# WallBaseBoard.net
KiCad netlist of a schematic drawn in Altium Designer
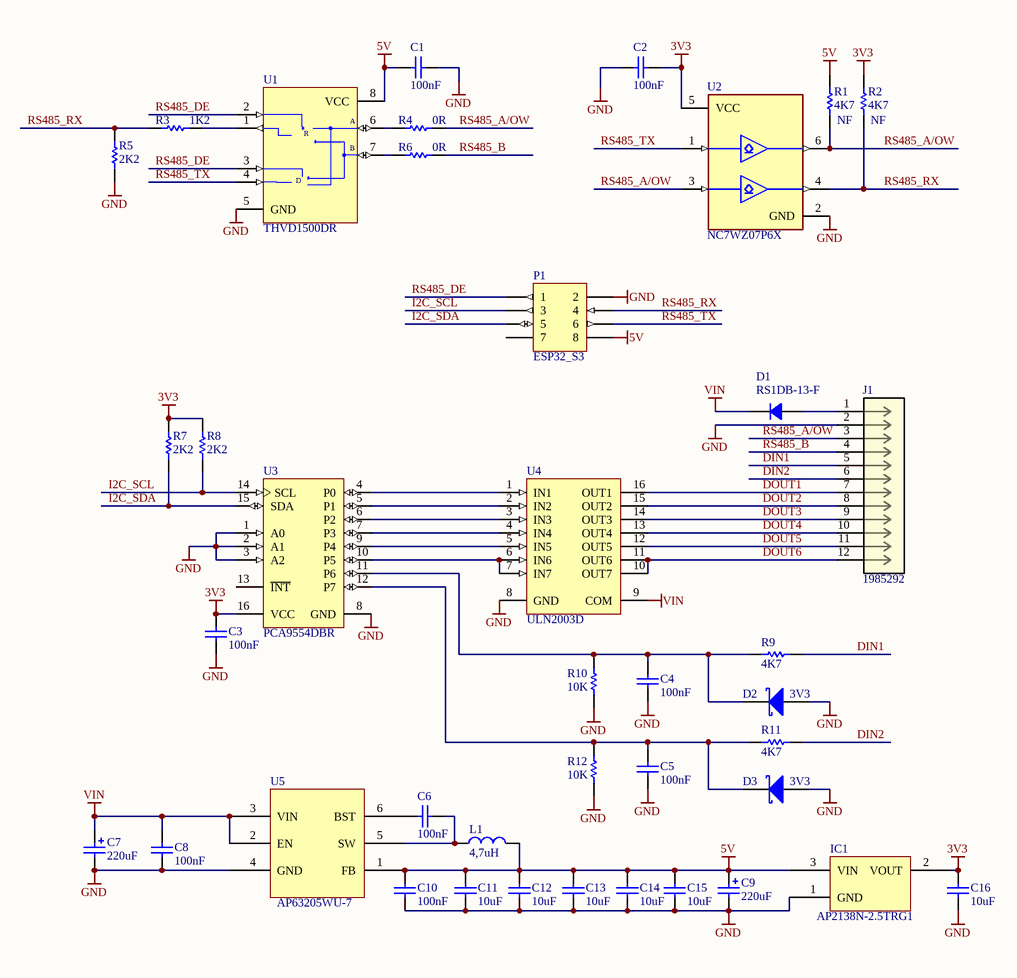
[diagram p0: WallBaseBoard.SchDoc]

(export (version "E")
  (design (tool "Eeschema 10.0.6"))
  (components
    (comp (ref "C1")
      (value "100nF")
      (footprint "0603")
      (description "Ceramic Chip Capacitor - Standard")
      (fields (field (name "PUBLISHER") "Altium Limited"))
      (libsource (lib "DE-211024") (part "C0603"))
    )
    (comp (ref "C2")
      (value "100nF")
      (footprint "0603")
      (description "Ceramic Chip Capacitor - Standard")
      (fields (field (name "PUBLISHER") "Altium Limited"))
      (libsource (lib "DE-211024") (part "C0603"))
    )
    (comp (ref "C3")
      (value "100nF")
      (footprint "0603")
      (description "Ceramic Chip Capacitor - Standard")
      (fields (field (name "PUBLISHER") "Altium Limited"))
      (libsource (lib "DE-211024") (part "C0603"))
    )
    (comp (ref "C4")
      (value "100nF")
      (footprint "0603")
      (description "Ceramic Chip Capacitor - Standard")
      (fields (field (name "PUBLISHER") "Altium Limited"))
      (libsource (lib "DE-211024") (part "C0603"))
    )
    (comp (ref "C5")
      (value "100nF")
      (footprint "0603")
      (description "Ceramic Chip Capacitor - Standard")
      (fields (field (name "PUBLISHER") "Altium Limited"))
      (libsource (lib "DE-211024") (part "C0603"))
    )
    (comp (ref "C6")
      (value "100nF")
      (footprint "0603")
      (description "Ceramic Chip Capacitor - Standard")
      (fields (field (name "PUBLISHER") "Altium Limited"))
      (libsource (lib "DE-211024") (part "C0603"))
    )
    (comp (ref "C7")
      (value "220uF")
      (footprint "SMD,D8xL10.2mm")
      (description "220uF 35V 195mA@120Hz ±20% SMD,D8xL10.2mm Aluminum Electrolytic Capacitors - SMD ROHS")
      (fields (field (name "PUBLISHER") "Altium Limited"))
      (libsource (lib "DE-211024") (part "ROQANG VT1V221M0810"))
    )
    (comp (ref "C8")
      (value "100nF")
      (footprint "0603")
      (description "Ceramic Chip Capacitor - Standard")
      (fields (field (name "PUBLISHER") "Altium Limited"))
      (libsource (lib "DE-211024") (part "C0603"))
    )
    (comp (ref "C9")
      (value "220uF")
      (footprint "SMD,D6.3xL7.7mm Aluminum Electrolytic Capacitors")
      (description "220uF 16V 110mA@120Hz ±20% SMD,D6.3xL7.7mm Aluminum Electrolytic Capacitors - SMD ROHS")
      (fields (field (name "Comment") "ROQANG VT1C221M0607_1") (field (name "PUBLISHER") "Altium Limited"))
      (libsource (lib "DE-211024") (part "ROQANG VT1C221M0607_1"))
    )
    (comp (ref "C10")
      (value "100nF")
      (footprint "0603")
      (description "Ceramic Chip Capacitor - Standard")
      (fields (field (name "PUBLISHER") "Altium Limited"))
      (libsource (lib "DE-211024") (part "C0603"))
    )
    (comp (ref "C11")
      (value "10uF")
      (footprint "0805")
      (description "Ceramic Chip Capacitor - Standard")
      (fields (field (name "Comment") "4u7") (field (name "PUBLISHER") "Altium Limited"))
      (libsource (lib "DE-211024") (part "C0805"))
    )
    (comp (ref "C12")
      (value "10uF")
      (footprint "0805")
      (description "Ceramic Chip Capacitor - Standard")
      (fields (field (name "Comment") "4u7") (field (name "PUBLISHER") "Altium Limited"))
      (libsource (lib "DE-211024") (part "C0805"))
    )
    (comp (ref "C13")
      (value "10uF")
      (footprint "0805")
      (description "Ceramic Chip Capacitor - Standard")
      (fields (field (name "Comment") "4u7") (field (name "PUBLISHER") "Altium Limited"))
      (libsource (lib "DE-211024") (part "C0805"))
    )
    (comp (ref "C14")
      (value "10uF")
      (footprint "0805")
      (description "Ceramic Chip Capacitor - Standard")
      (fields (field (name "Comment") "4u7") (field (name "PUBLISHER") "Altium Limited"))
      (libsource (lib "DE-211024") (part "C0805"))
    )
    (comp (ref "C15")
      (value "10uF")
      (footprint "0805")
      (description "Ceramic Chip Capacitor - Standard")
      (fields (field (name "Comment") "4u7") (field (name "PUBLISHER") "Altium Limited"))
      (libsource (lib "DE-211024") (part "C0805"))
    )
    (comp (ref "C16")
      (value "10uF")
      (footprint "0805")
      (description "Ceramic Chip Capacitor - Standard")
      (fields (field (name "Comment") "4u7") (field (name "PUBLISHER") "Altium Limited"))
      (libsource (lib "DE-211024") (part "C0805"))
    )
    (comp (ref "D1")
      (value "RS1DB-13-F")
      (footprint "DO214AA SMB")
      (description "DIODE STANDARD 200V 1A SMB")
      (fields (field (name "MANUFACTURER") "Diodes Incorporated"))
      (libsource (lib "Celestial Altium Library - altium_library") (part "Diode"))
    )
    (comp (ref "D2")
      (value "3V3")
      (footprint "SOD323")
      (description "Schottky Barrier Diode")
      (fields (field (name "PUBLISHER") "Altium Limited"))
      (libsource (lib "DE-250624") (part "1PS76SB10"))
    )
    (comp (ref "D3")
      (value "3V3")
      (footprint "SOD323")
      (description "Schottky Barrier Diode")
      (fields (field (name "PUBLISHER") "Altium Limited"))
      (libsource (lib "DE-250624") (part "1PS76SB10"))
    )
    (comp (ref "IC1")
      (value "AP2138N-2.5TRG1")
      (footprint "DIODES SOT-23-3 N")
      (description "IC REG LINEAR 2.5V 250MA SOT23-3")
      (fields (field (name "MANUFACTURER") "Diodes Incorporated"))
      (libsource (lib "Celestial Altium Library - altium_library") (part "Diodes Inc AP2138 3PIN"))
    )
    (comp (ref "J1")
      (value "1985292")
      (footprint "CONN_1985292_PXC")
      (fields (field (name "COPYRIGHT") "Copyright (C) 2026 Ultra Librarian. All rights reserved."))
      (libsource (lib "WallBaseBoard_1") (part "1985292"))
    )
    (comp (ref "L1")
      (value "4,7uH")
      (footprint "XRNR4030-4.7uH/M")
      (description "2A 4.7uH Magnetic Adhesive Inductor ±20% 2.9A SMD-2P,4x4mm Power Inductors ROHS")
      (fields (field (name "Comment") "Inductor"))
      (libsource (lib "DE-211024") (part "Inductor"))
    )
    (comp (ref "P1")
      (value "ESP32_S3")
      (footprint "HDR2X4")
      (description "Header, 4-Pin, Dual row")
      (fields (field (name "PUBLISHER") "Altium Limited"))
      (libsource (lib "WallBaseBoard") (part "Header 4X2"))
    )
    (comp (ref "R1")
      (value "NF")
      (footprint "ERA-0603")
      (fields (field (name "ALTIUM_VALUE") "4K7") (field (name "PUBLISHER") "Altium Limited"))
      (libsource (lib "DE-211024") (part "ERAV"))
    )
    (comp (ref "R2")
      (value "NF")
      (footprint "ERA-0603")
      (fields (field (name "ALTIUM_VALUE") "4K7") (field (name "PUBLISHER") "Altium Limited"))
      (libsource (lib "DE-211024") (part "ERAV"))
    )
    (comp (ref "R3")
      (value "1K2")
      (footprint "ERA-0603")
      (fields (field (name "Comment") "10K") (field (name "PUBLISHER") "Altium Limited"))
      (libsource (lib "DE-211024") (part "ERAV"))
    )
    (comp (ref "R4")
      (value "0R")
      (footprint "ERA-0603")
      (fields (field (name "Comment") "10K") (field (name "PUBLISHER") "Altium Limited"))
      (libsource (lib "DE-211024") (part "ERAV"))
    )
    (comp (ref "R5")
      (value "2K2")
      (footprint "ERA-0603")
      (fields (field (name "Comment") "10K") (field (name "PUBLISHER") "Altium Limited"))
      (libsource (lib "DE-211024") (part "ERAV"))
    )
    (comp (ref "R6")
      (value "0R")
      (footprint "ERA-0603")
      (fields (field (name "Comment") "10K") (field (name "PUBLISHER") "Altium Limited"))
      (libsource (lib "DE-211024") (part "ERAV"))
    )
    (comp (ref "R7")
      (value "2K2")
      (footprint "ERA-0603")
      (fields (field (name "Comment") "10K") (field (name "PUBLISHER") "Altium Limited"))
      (libsource (lib "DE-211024") (part "ERAV"))
    )
    (comp (ref "R8")
      (value "2K2")
      (footprint "ERA-0603")
      (fields (field (name "Comment") "10K") (field (name "PUBLISHER") "Altium Limited"))
      (libsource (lib "DE-211024") (part "ERAV"))
    )
    (comp (ref "R9")
      (value "4K7")
      (footprint "ERA-0603")
      (fields (field (name "Comment") "10K") (field (name "PUBLISHER") "Altium Limited"))
      (libsource (lib "DE-211024") (part "ERAV"))
    )
    (comp (ref "R10")
      (value "10K")
      (footprint "ERA-0603")
      (fields (field (name "PUBLISHER") "Altium Limited"))
      (libsource (lib "DE-211024") (part "ERAV"))
    )
    (comp (ref "R11")
      (value "4K7")
      (footprint "ERA-0603")
      (fields (field (name "Comment") "10K") (field (name "PUBLISHER") "Altium Limited"))
      (libsource (lib "DE-211024") (part "ERAV"))
    )
    (comp (ref "R12")
      (value "10K")
      (footprint "ERA-0603")
      (fields (field (name "PUBLISHER") "Altium Limited"))
      (libsource (lib "DE-211024") (part "ERAV"))
    )
    (comp (ref "U1")
      (value "THVD1500DR")
      (footprint "NSO8_N")
      (description "Low-Power, Slew-Rate-Limited RS-485/RS-422 Transceiver")
      (fields (field (name "PUBLISHER") "Altium Limited"))
      (libsource (lib "WallBaseBoard") (part "MAX485ESA"))
    )
    (comp (ref "U2")
      (value "NC7WZ07P6X")
      (footprint "FP-419AD-01-MFG")
      (description "IC BUF NON-INVERT 5.5V SC70-6")
      (libsource (lib "Altium Content Vault") (part "cca7a6a429c5e3920cc4b6714f97f4b"))
    )
    (comp (ref "U3")
      (value "PCA9554DBR")
      (footprint "SSOP-16")
      (fields (field (name "MANUFACTURER") "Texas Instruments"))
      (libsource (lib "WallBaseBoard") (part "CMP-0314-00200-2"))
    )
    (comp (ref "U4")
      (value "ULN2003D")
      (footprint "SO16_N")
      (description "Seven Darlington Array")
      (fields (field (name "PUBLISHER") "Altium Limited"))
      (libsource (lib "WallBaseBoard") (part "ULN2003D"))
    )
    (comp (ref "U5")
      (value "AP63205WU-7")
      (footprint "TSOT-26")
      (description "2A synchronous  buck converter")
      (libsource (lib "DE-250624") (part "AP63200"))
    )
  )
  (nets
    (net (code "1") (name "/DIN1") (class "Default")
      (node (ref "J1") (pin "5") (pinfunction "5_5") (pintype "passive"))
      (node (ref "R9") (pin "1") (pinfunction "1_1") (pintype "passive"))
    )
    (net (code "2") (name "/DIN2") (class "Default")
      (node (ref "J1") (pin "6") (pinfunction "6_6") (pintype "passive"))
      (node (ref "R11") (pin "1") (pinfunction "1_1") (pintype "passive"))
    )
    (net (code "3") (name "/DOUT1") (class "Default")
      (node (ref "J1") (pin "7") (pinfunction "7_7") (pintype "passive"))
      (node (ref "U4") (pin "16") (pinfunction "OUT1_16") (pintype "open_collector"))
    )
    (net (code "4") (name "/DOUT2") (class "Default")
      (node (ref "J1") (pin "8") (pinfunction "8_8") (pintype "passive"))
      (node (ref "U4") (pin "15") (pinfunction "OUT2_15") (pintype "open_collector"))
    )
    (net (code "5") (name "/DOUT3") (class "Default")
      (node (ref "J1") (pin "9") (pinfunction "9_9") (pintype "passive"))
      (node (ref "U4") (pin "14") (pinfunction "OUT3_14") (pintype "open_collector"))
    )
    (net (code "6") (name "/DOUT4") (class "Default")
      (node (ref "J1") (pin "10") (pinfunction "10_10") (pintype "passive"))
      (node (ref "U4") (pin "13") (pinfunction "OUT4_13") (pintype "open_collector"))
    )
    (net (code "7") (name "/DOUT5") (class "Default")
      (node (ref "J1") (pin "11") (pinfunction "11_11") (pintype "passive"))
      (node (ref "U4") (pin "12") (pinfunction "OUT5_12") (pintype "open_collector"))
    )
    (net (code "8") (name "/DOUT6") (class "Default")
      (node (ref "J1") (pin "12") (pinfunction "12_12") (pintype "passive"))
      (node (ref "U4") (pin "10") (pinfunction "OUT7_10") (pintype "open_collector"))
      (node (ref "U4") (pin "11") (pinfunction "OUT6_11") (pintype "open_collector"))
    )
    (net (code "9") (name "/I2C_SCL") (class "Default")
      (node (ref "P1") (pin "3") (pinfunction "3_3") (pintype "output"))
      (node (ref "R8") (pin "1") (pinfunction "1_1") (pintype "passive"))
      (node (ref "U3") (pin "14") (pinfunction "SCL_14") (pintype "input"))
    )
    (net (code "10") (name "/I2C_SDA") (class "Default")
      (node (ref "P1") (pin "5") (pinfunction "5_5") (pintype "bidirectional"))
      (node (ref "R7") (pin "1") (pinfunction "1_1") (pintype "passive"))
      (node (ref "U3") (pin "15") (pinfunction "SDA_15") (pintype "bidirectional"))
    )
    (net (code "11") (name "/RS485_A{slash}OW") (class "Default")
      (node (ref "J1") (pin "3") (pinfunction "3_3") (pintype "passive"))
      (node (ref "R1") (pin "1") (pinfunction "1_1") (pintype "passive"))
      (node (ref "R4") (pin "2") (pinfunction "2_2") (pintype "passive"))
      (node (ref "U2") (pin "3") (pinfunction "A2_3") (pintype "input"))
      (node (ref "U2") (pin "6") (pinfunction "Y1_6") (pintype "output"))
    )
    (net (code "12") (name "/RS485_B") (class "Default")
      (node (ref "J1") (pin "4") (pinfunction "4_4") (pintype "passive"))
      (node (ref "R6") (pin "2") (pinfunction "2_2") (pintype "passive"))
    )
    (net (code "13") (name "/RS485_DE") (class "Default")
      (node (ref "P1") (pin "1") (pinfunction "1_1") (pintype "output"))
      (node (ref "U1") (pin "2") (pinfunction "~{RE}_2") (pintype "input"))
      (node (ref "U1") (pin "3") (pinfunction "DE_3") (pintype "input"))
    )
    (net (code "14") (name "/RS485_RX") (class "Default")
      (node (ref "P1") (pin "4") (pinfunction "4_4") (pintype "input"))
      (node (ref "R2") (pin "1") (pinfunction "1_1") (pintype "passive"))
      (node (ref "R3") (pin "1") (pinfunction "1_1") (pintype "passive"))
      (node (ref "R5") (pin "2") (pinfunction "2_2") (pintype "passive"))
      (node (ref "U2") (pin "4") (pinfunction "Y2_4") (pintype "output"))
    )
    (net (code "15") (name "/RS485_TX") (class "Default")
      (node (ref "P1") (pin "6") (pinfunction "6_6") (pintype "output"))
      (node (ref "U1") (pin "4") (pinfunction "DI_4") (pintype "input"))
      (node (ref "U2") (pin "1") (pinfunction "A1_1") (pintype "input"))
    )
    (net (code "16") (name "3V3") (class "Default")
      (node (ref "C16") (pin "2") (pinfunction "2_2") (pintype "passive"))
      (node (ref "C2") (pin "1") (pinfunction "1_1") (pintype "passive"))
      (node (ref "C3") (pin "2") (pinfunction "2_2") (pintype "passive"))
      (node (ref "IC1") (pin "2") (pinfunction "VOUT_2") (pintype "passive"))
      (node (ref "R2") (pin "2") (pinfunction "2_2") (pintype "passive"))
      (node (ref "R7") (pin "2") (pinfunction "2_2") (pintype "passive"))
      (node (ref "R8") (pin "2") (pinfunction "2_2") (pintype "passive"))
      (node (ref "U2") (pin "5") (pinfunction "VCC_5") (pintype "power_in"))
      (node (ref "U3") (pin "16") (pinfunction "VCC_16") (pintype "power_in"))
    )
    (net (code "17") (name "5V") (class "Default")
      (node (ref "C1") (pin "2") (pinfunction "2_2") (pintype "passive"))
      (node (ref "C10") (pin "2") (pinfunction "2_2") (pintype "passive"))
      (node (ref "C11") (pin "2") (pinfunction "2_2") (pintype "passive"))
      (node (ref "C12") (pin "2") (pinfunction "2_2") (pintype "passive"))
      (node (ref "C13") (pin "2") (pinfunction "2_2") (pintype "passive"))
      (node (ref "C14") (pin "2") (pinfunction "2_2") (pintype "passive"))
      (node (ref "C15") (pin "2") (pinfunction "2_2") (pintype "passive"))
      (node (ref "C9") (pin "1") (pinfunction "1_1") (pintype "passive"))
      (node (ref "IC1") (pin "3") (pinfunction "VIN_3") (pintype "passive"))
      (node (ref "L1") (pin "1") (pinfunction "1_1") (pintype "passive"))
      (node (ref "P1") (pin "8") (pinfunction "8_8") (pintype "passive"))
      (node (ref "R1") (pin "2") (pinfunction "2_2") (pintype "passive"))
      (node (ref "U1") (pin "8") (pinfunction "VCC_8") (pintype "power_in"))
      (node (ref "U5") (pin "1") (pinfunction "FB_1") (pintype "passive"))
    )
    (net (code "18") (name "GND") (class "Default")
      (node (ref "C1") (pin "1") (pinfunction "1_1") (pintype "passive"))
      (node (ref "C10") (pin "1") (pinfunction "1_1") (pintype "passive"))
      (node (ref "C11") (pin "1") (pinfunction "1_1") (pintype "passive"))
      (node (ref "C12") (pin "1") (pinfunction "1_1") (pintype "passive"))
      (node (ref "C13") (pin "1") (pinfunction "1_1") (pintype "passive"))
      (node (ref "C14") (pin "1") (pinfunction "1_1") (pintype "passive"))
      (node (ref "C15") (pin "1") (pinfunction "1_1") (pintype "passive"))
      (node (ref "C16") (pin "1") (pinfunction "1_1") (pintype "passive"))
      (node (ref "C2") (pin "2") (pinfunction "2_2") (pintype "passive"))
      (node (ref "C3") (pin "1") (pinfunction "1_1") (pintype "passive"))
      (node (ref "C4") (pin "1") (pinfunction "1_1") (pintype "passive"))
      (node (ref "C5") (pin "1") (pinfunction "1_1") (pintype "passive"))
      (node (ref "C7") (pin "2") (pinfunction "2_2") (pintype "passive"))
      (node (ref "C8") (pin "1") (pinfunction "1_1") (pintype "passive"))
      (node (ref "C9") (pin "2") (pinfunction "2_2") (pintype "passive"))
      (node (ref "D2") (pin "2") (pinfunction "A_2") (pintype "passive"))
      (node (ref "D3") (pin "2") (pinfunction "A_2") (pintype "passive"))
      (node (ref "IC1") (pin "1") (pinfunction "GND_1") (pintype "passive"))
      (node (ref "J1") (pin "2") (pinfunction "2_2") (pintype "passive"))
      (node (ref "P1") (pin "2") (pinfunction "2_2") (pintype "passive"))
      (node (ref "R10") (pin "1") (pinfunction "1_1") (pintype "passive"))
      (node (ref "R12") (pin "1") (pinfunction "1_1") (pintype "passive"))
      (node (ref "R5") (pin "1") (pinfunction "1_1") (pintype "passive"))
      (node (ref "U1") (pin "5") (pinfunction "GND_5") (pintype "power_in"))
      (node (ref "U2") (pin "2") (pinfunction "GND_2") (pintype "power_in"))
      (node (ref "U3") (pin "1") (pinfunction "A0_1") (pintype "input"))
      (node (ref "U3") (pin "2") (pinfunction "A1_2") (pintype "input"))
      (node (ref "U3") (pin "3") (pinfunction "A2_3") (pintype "input"))
      (node (ref "U3") (pin "8") (pinfunction "GND_8") (pintype "power_in"))
      (node (ref "U4") (pin "8") (pinfunction "GND_8") (pintype "power_in"))
      (node (ref "U5") (pin "4") (pinfunction "GND_4") (pintype "power_in"))
    )
    (net (code "19") (name "Net-(D1-Pad1)") (class "Default")
      (node (ref "D1") (pin "1") (pinfunction "1_1") (pintype "passive"))
      (node (ref "J1") (pin "1") (pinfunction "1_1") (pintype "passive"))
    )
    (net (code "20") (name "Net-(D2-K)") (class "Default")
      (node (ref "C4") (pin "2") (pinfunction "2_2") (pintype "passive"))
      (node (ref "D2") (pin "1") (pinfunction "K_1") (pintype "passive"))
      (node (ref "R10") (pin "2") (pinfunction "2_2") (pintype "passive"))
      (node (ref "R9") (pin "2") (pinfunction "2_2") (pintype "passive"))
      (node (ref "U3") (pin "11") (pinfunction "P6_11") (pintype "bidirectional"))
    )
    (net (code "21") (name "Net-(D3-K)") (class "Default")
      (node (ref "C5") (pin "2") (pinfunction "2_2") (pintype "passive"))
      (node (ref "D3") (pin "1") (pinfunction "K_1") (pintype "passive"))
      (node (ref "R11") (pin "2") (pinfunction "2_2") (pintype "passive"))
      (node (ref "R12") (pin "2") (pinfunction "2_2") (pintype "passive"))
      (node (ref "U3") (pin "12") (pinfunction "P7_12") (pintype "bidirectional"))
    )
    (net (code "22") (name "Net-(U1-A)") (class "Default")
      (node (ref "R4") (pin "1") (pinfunction "1_1") (pintype "passive"))
      (node (ref "U1") (pin "6") (pinfunction "A_6") (pintype "bidirectional"))
    )
    (net (code "23") (name "Net-(U1-B)") (class "Default")
      (node (ref "R6") (pin "1") (pinfunction "1_1") (pintype "passive"))
      (node (ref "U1") (pin "7") (pinfunction "B_7") (pintype "bidirectional"))
    )
    (net (code "24") (name "Net-(U1-RO)") (class "Default")
      (node (ref "R3") (pin "2") (pinfunction "2_2") (pintype "passive"))
      (node (ref "U1") (pin "1") (pinfunction "RO_1") (pintype "output"))
    )
    (net (code "25") (name "Net-(U3-P0)") (class "Default")
      (node (ref "U3") (pin "4") (pinfunction "P0_4") (pintype "bidirectional"))
      (node (ref "U4") (pin "1") (pinfunction "IN1_1") (pintype "input"))
    )
    (net (code "26") (name "Net-(U3-P1)") (class "Default")
      (node (ref "U3") (pin "5") (pinfunction "P1_5") (pintype "bidirectional"))
      (node (ref "U4") (pin "2") (pinfunction "IN2_2") (pintype "input"))
    )
    (net (code "27") (name "Net-(U3-P2)") (class "Default")
      (node (ref "U3") (pin "6") (pinfunction "P2_6") (pintype "bidirectional"))
      (node (ref "U4") (pin "3") (pinfunction "IN3_3") (pintype "input"))
    )
    (net (code "28") (name "Net-(U3-P3)") (class "Default")
      (node (ref "U3") (pin "7") (pinfunction "P3_7") (pintype "bidirectional"))
      (node (ref "U4") (pin "4") (pinfunction "IN4_4") (pintype "input"))
    )
    (net (code "29") (name "Net-(U3-P4)") (class "Default")
      (node (ref "U3") (pin "9") (pinfunction "P4_9") (pintype "bidirectional"))
      (node (ref "U4") (pin "5") (pinfunction "IN5_5") (pintype "input"))
    )
    (net (code "30") (name "Net-(U3-P5)") (class "Default")
      (node (ref "U3") (pin "10") (pinfunction "P5_10") (pintype "bidirectional"))
      (node (ref "U4") (pin "6") (pinfunction "IN6_6") (pintype "input"))
      (node (ref "U4") (pin "7") (pinfunction "IN7_7") (pintype "input"))
    )
    (net (code "31") (name "Net-(U5-BST)") (class "Default")
      (node (ref "C6") (pin "1") (pinfunction "1_1") (pintype "passive"))
      (node (ref "U5") (pin "6") (pinfunction "BST_6") (pintype "passive"))
    )
    (net (code "32") (name "Net-(U5-SW)") (class "Default")
      (node (ref "C6") (pin "2") (pinfunction "2_2") (pintype "passive"))
      (node (ref "L1") (pin "2") (pinfunction "2_2") (pintype "passive"))
      (node (ref "U5") (pin "5") (pinfunction "SW_5") (pintype "passive"))
    )
    (net (code "33") (name "VIN") (class "Default")
      (node (ref "C7") (pin "1") (pinfunction "1_1") (pintype "passive"))
      (node (ref "C8") (pin "2") (pinfunction "2_2") (pintype "passive"))
      (node (ref "D1") (pin "2") (pinfunction "2_2") (pintype "passive"))
      (node (ref "U4") (pin "9") (pinfunction "COM_9") (pintype "passive"))
      (node (ref "U5") (pin "2") (pinfunction "EN_2") (pintype "passive"))
      (node (ref "U5") (pin "3") (pinfunction "VIN_3") (pintype "power_in"))
    )
    (net (code "34") (name "unconnected-(P1-Pad7)") (class "Default")
      (node (ref "P1") (pin "7") (pinfunction "7_7") (pintype "passive"))
    )
    (net (code "35") (name "unconnected-(U3-~{INT}-Pad13)") (class "Default")
      (node (ref "U3") (pin "13") (pinfunction "~{INT}_13") (pintype "open_collector"))
    )
  )
)
